# H_bridge.net
KiCad netlist of a schematic drawn in Altium Designer
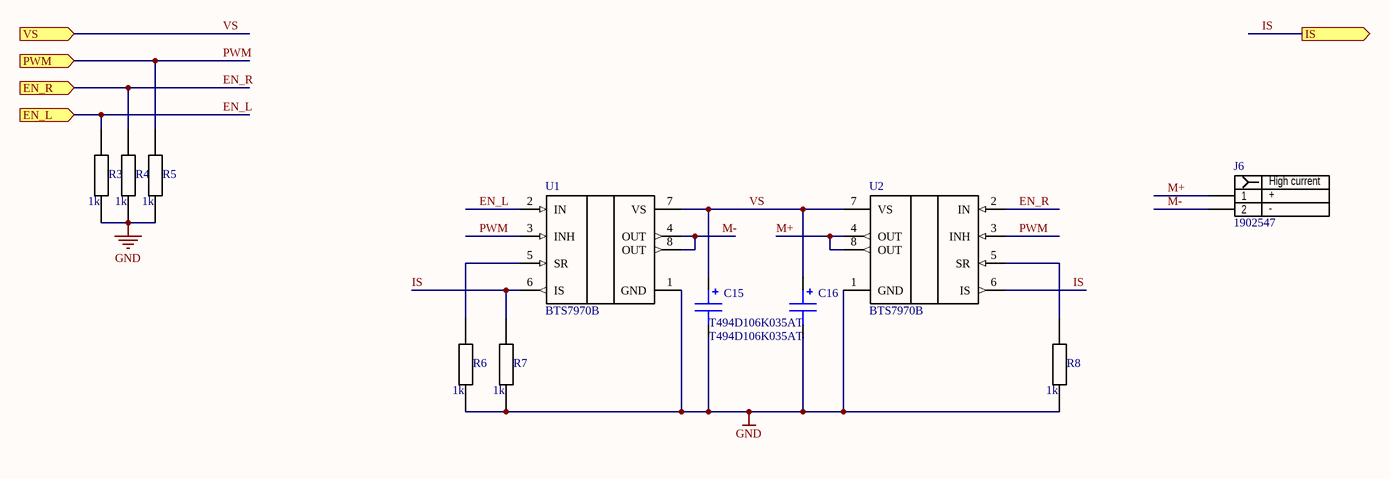
[diagram p0: H_bridge.SchDoc]

(export (version "E")
  (design (tool "Eeschema 10.0.6"))
  (components
    (comp (ref "C15")
      (value "T494D106K035AT")
      (footprint "SamacSys:CAPPM7343X310N")
      (description "Capacitor Polarised")
      (fields (field (name "MOUSER PART NUMBER") "80-T494D106K035"))
      (libsource (lib "RobotLib") (part "T494D106K035AT"))
    )
    (comp (ref "C16")
      (value "T494D106K035AT")
      (footprint "SamacSys:CAPPM7343X310N")
      (description "Capacitor Polarised")
      (fields (field (name "MOUSER PART NUMBER") "80-T494D106K035"))
      (libsource (lib "RobotLib") (part "T494D106K035AT"))
    )
    (comp (ref "J6")
      (value "1902547")
      (footprint "1902547")
      (description "Phoenix Contact MKDS 5 HV/2-9.52")
      (fields (field (name "MOUSER PART NUMBER") "651-1902547"))
      (libsource (lib "RobotLib") (part "1902547"))
    )
    (comp (ref "R3")
      (value "1k")
      (footprint "SamacSys:RESC1608X55N")
      (description "RS PRO SMD-Widerstand, 1kΩ ±5%")
      (libsource (lib "RobotLib") (part "res 0603"))
    )
    (comp (ref "R4")
      (value "1k")
      (footprint "SamacSys:RESC1608X55N")
      (description "RS PRO SMD-Widerstand, 1kΩ ±5%")
      (libsource (lib "RobotLib") (part "res 0603"))
    )
    (comp (ref "R5")
      (value "1k")
      (footprint "SamacSys:RESC1608X55N")
      (description "RS PRO SMD-Widerstand, 1kΩ ±5%")
      (libsource (lib "RobotLib") (part "res 0603"))
    )
    (comp (ref "R6")
      (value "1k")
      (footprint "SamacSys:RESC1608X55N")
      (description "RS PRO SMD-Widerstand, 1kΩ ±5%")
      (libsource (lib "RobotLib") (part "res 0603"))
    )
    (comp (ref "R7")
      (value "1k")
      (footprint "SamacSys:RESC1608X55N")
      (description "RS PRO SMD-Widerstand, 1kΩ ±5%")
      (libsource (lib "RobotLib") (part "res 0603"))
    )
    (comp (ref "R8")
      (value "1k")
      (footprint "SamacSys:RESC1608X55N")
      (description "RS PRO SMD-Widerstand, 1kΩ ±5%")
      (libsource (lib "RobotLib") (part "res 0603"))
    )
    (comp (ref "U1")
      (value "BTS7970B")
      (footprint "PG-TO263-7-1")
      (description "Infineon Motor Driver IC BTN7970BAUMA1, 50A, 25kHz, TO-263, 7-Pin, BLDC")
      (fields (field (name "MF") "Infineon"))
      (libsource (lib "RobotLib") (part "BTS7970B"))
    )
    (comp (ref "U2")
      (value "BTS7970B")
      (footprint "PG-TO263-7-1")
      (description "Infineon Motor Driver IC BTN7970BAUMA1, 50A, 25kHz, TO-263, 7-Pin, BLDC")
      (fields (field (name "MF") "Infineon"))
      (libsource (lib "RobotLib") (part "BTS7970B"))
    )
  )
  (nets
    (net (code "1") (name "/EN_L") (class "Default")
      (node (ref "R3") (pin "2") (pinfunction "2_2") (pintype "passive"))
      (node (ref "U1") (pin "2") (pinfunction "IN_2") (pintype "input"))
    )
    (net (code "2") (name "/EN_R") (class "Default")
      (node (ref "R4") (pin "2") (pinfunction "2_2") (pintype "passive"))
      (node (ref "U2") (pin "2") (pinfunction "IN_2") (pintype "input"))
    )
    (net (code "3") (name "/IS") (class "Default")
      (node (ref "R7") (pin "2") (pinfunction "2_2") (pintype "passive"))
      (node (ref "U1") (pin "6") (pinfunction "IS_6") (pintype "output"))
      (node (ref "U2") (pin "6") (pinfunction "IS_6") (pintype "output"))
    )
    (net (code "4") (name "/M+") (class "Default")
      (node (ref "J6") (pin "1") (pinfunction "1_1") (pintype "passive"))
      (node (ref "U2") (pin "4") (pinfunction "OUT_4") (pintype "output"))
      (node (ref "U2") (pin "8") (pinfunction "OUT_8") (pintype "output"))
    )
    (net (code "5") (name "/M-") (class "Default")
      (node (ref "J6") (pin "2") (pinfunction "2_2") (pintype "passive"))
      (node (ref "U1") (pin "4") (pinfunction "OUT_4") (pintype "output"))
      (node (ref "U1") (pin "8") (pinfunction "OUT_8") (pintype "output"))
    )
    (net (code "6") (name "/PWM") (class "Default")
      (node (ref "R5") (pin "2") (pinfunction "2_2") (pintype "passive"))
      (node (ref "U1") (pin "3") (pinfunction "INH_3") (pintype "input"))
      (node (ref "U2") (pin "3") (pinfunction "INH_3") (pintype "input"))
    )
    (net (code "7") (name "/VS") (class "Default")
      (node (ref "C15") (pin "1") (pinfunction "+_1") (pintype "passive"))
      (node (ref "C16") (pin "1") (pinfunction "+_1") (pintype "passive"))
      (node (ref "U1") (pin "7") (pinfunction "VS_7") (pintype "power_in"))
      (node (ref "U2") (pin "7") (pinfunction "VS_7") (pintype "power_in"))
    )
    (net (code "8") (name "GND") (class "Default")
      (node (ref "C15") (pin "2") (pinfunction "-_2") (pintype "passive"))
      (node (ref "C16") (pin "2") (pinfunction "-_2") (pintype "passive"))
      (node (ref "R3") (pin "1") (pinfunction "1_1") (pintype "passive"))
      (node (ref "R4") (pin "1") (pinfunction "1_1") (pintype "passive"))
      (node (ref "R5") (pin "1") (pinfunction "1_1") (pintype "passive"))
      (node (ref "R6") (pin "1") (pinfunction "1_1") (pintype "passive"))
      (node (ref "R7") (pin "1") (pinfunction "1_1") (pintype "passive"))
      (node (ref "R8") (pin "1") (pinfunction "1_1") (pintype "passive"))
      (node (ref "U1") (pin "1") (pinfunction "GND_1") (pintype "power_in"))
      (node (ref "U2") (pin "1") (pinfunction "GND_1") (pintype "power_in"))
    )
    (net (code "9") (name "Net-(U1-SR)") (class "Default")
      (node (ref "R6") (pin "2") (pinfunction "2_2") (pintype "passive"))
      (node (ref "U1") (pin "5") (pinfunction "SR_5") (pintype "input"))
    )
    (net (code "10") (name "Net-(U2-SR)") (class "Default")
      (node (ref "R8") (pin "2") (pinfunction "2_2") (pintype "passive"))
      (node (ref "U2") (pin "5") (pinfunction "SR_5") (pintype "input"))
    )
  )
)
